# FlashMemory.net
KiCad netlist of a schematic drawn in Altium Designer
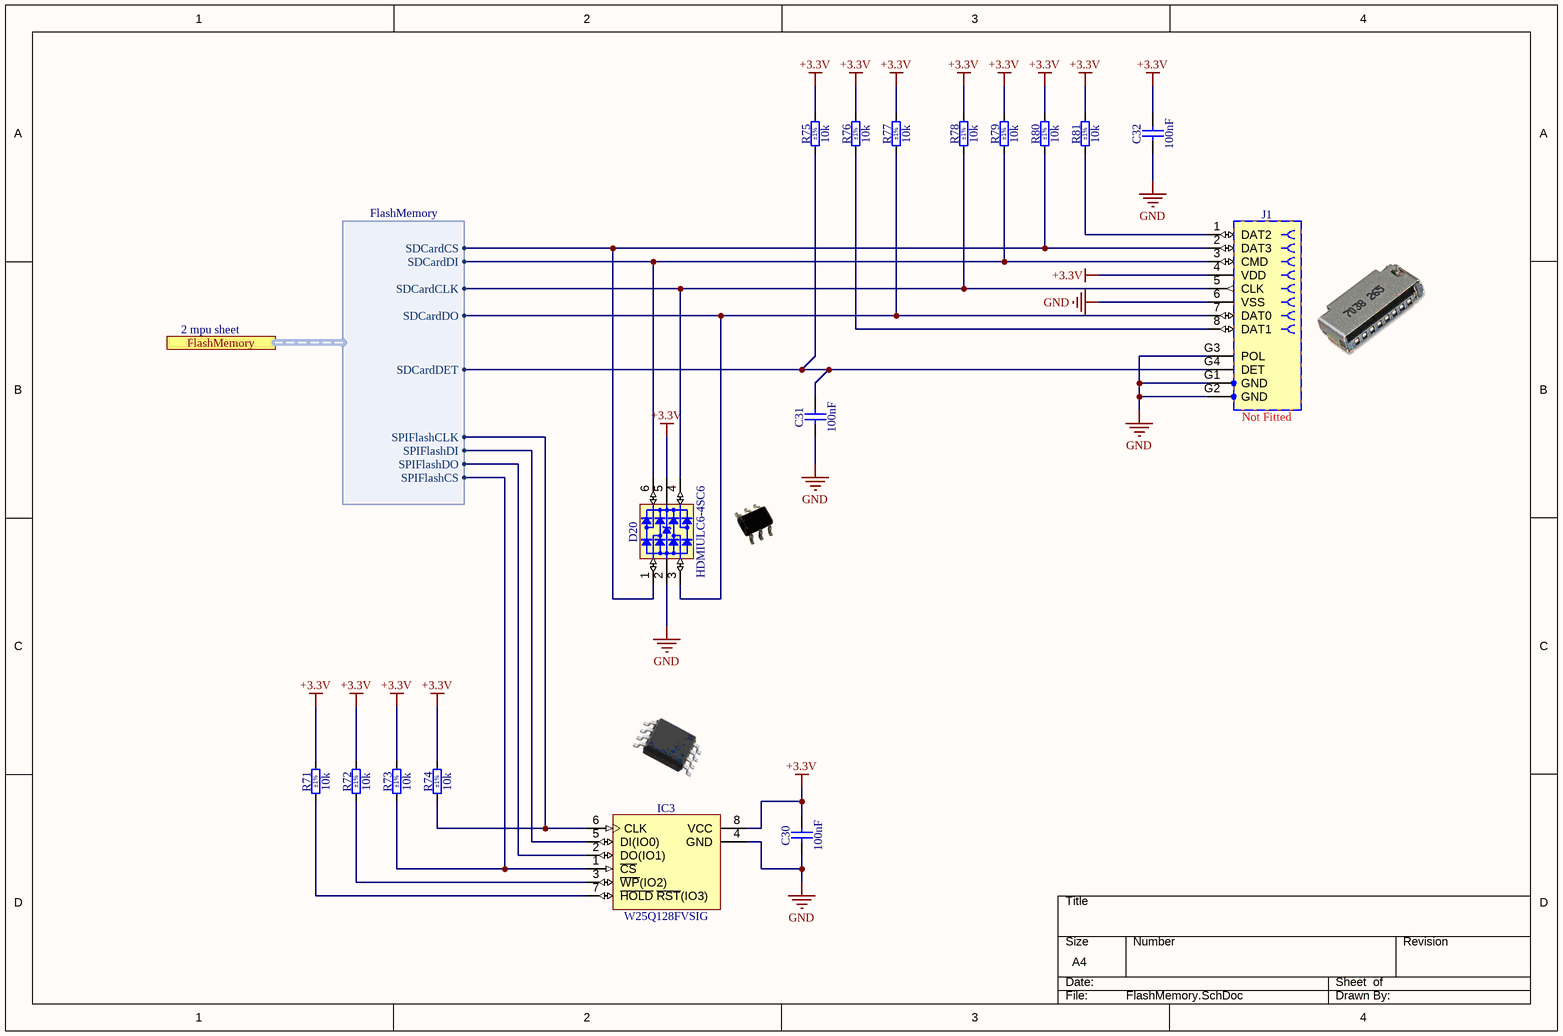
[diagram p0: FlashMemory.SchDoc]

(export (version "E")
  (design (tool "Eeschema 10.0.6"))
  (components
    (comp (ref "C30")
      (value "100nF")
      (footprint "CAPC1608X87N")
      (description "Non-polarised capacitor")
      (fields
        (field (name "PART NUMBER") "CC0603_100NF_50V_10%_X7R")
        (field (name "VOLTAGE") "50V")
        (field (name "AUTHOR") "CERN DEM JLC")
      )
      (libsource (lib "Capacitors") (part "Capacitor - non polarized"))
    )
    (comp (ref "C31")
      (value "100nF")
      (footprint "CAPC1608X87N")
      (description "Non-polarised capacitor")
      (fields
        (field (name "PART NUMBER") "CC0603_100NF_50V_10%_X7R")
        (field (name "VOLTAGE") "50V")
        (field (name "AUTHOR") "CERN DEM JLC")
      )
      (libsource (lib "Capacitors") (part "Capacitor - non polarized"))
    )
    (comp (ref "C32")
      (value "100nF")
      (footprint "CAPC1608X87N")
      (description "Non-polarised capacitor")
      (fields
        (field (name "PART NUMBER") "CC0603_100NF_50V_10%_X7R")
        (field (name "VOLTAGE") "50V")
        (field (name "AUTHOR") "CERN DEM JLC")
      )
      (libsource (lib "Capacitors") (part "Capacitor - non polarized"))
    )
    (comp (ref "D20")
      (value "HDMIULC6-4SC6")
      (footprint "SOT95P280X145-6N")
      (description "Ultra Large Bandwidth HDMI ESD Protection")
      (fields
        (field (name "VOLTAGE") "6V")
        (field (name "MANUFACTURER") "ST MICROELECTRONICS")
        (field (name "AUTHOR") "CERN DEM JLC")
      )
      (libsource (lib "ICs And Semiconductors") (part "HDMIULC6-4SC6"))
    )
    (comp (ref "IC3")
      (value "W25Q128FVSIG")
      (footprint "SOIC127P790X216-8N")
      (description "128M-bit Serial Flash Memory with uniform 4KB sectors and Dual/Quad SPI and QPI")
      (fields (field (name "MANUFACTURER") "WINBOND") (field (name "AUTHOR") "CERN DEM MR"))
      (libsource (lib "ICs And Semiconductors") (part "W25Q128FVSIG"))
    )
    (comp (ref "J1")
      (value "Not Fitted")
      (footprint "MOLEX_47309-2651")
      (description "MicroSD Card Header with Detect Switch")
      (fields
        (field (name "PART NUMBER") "MOLEX_47309-2651")
        (field (name "MANUFACTURER") "MOLEX")
        (field (name "AUTHOR") "CERN DEM JMW")
      )
      (libsource (lib "Connectors") (part "MOLEX_47309-2651"))
    )
    (comp (ref "R71")
      (value "10k")
      (footprint "RESC1608X55N")
      (description "Resistor - 1%")
      (fields
        (field (name "TOLERANCE") "±1%")
        (field (name "PART NUMBER") "R0603_10K_1%_0.1W_100PPM")
        (field (name "POWER") "0.1W")
        (field (name "AUTHOR") "CERN DEM JLC")
      )
      (libsource (lib "Resistors") (part "Resistor - 1%"))
    )
    (comp (ref "R72")
      (value "10k")
      (footprint "RESC1608X55N")
      (description "Resistor - 1%")
      (fields
        (field (name "TOLERANCE") "±1%")
        (field (name "PART NUMBER") "R0603_10K_1%_0.1W_100PPM")
        (field (name "POWER") "0.1W")
        (field (name "AUTHOR") "CERN DEM JLC")
      )
      (libsource (lib "Resistors") (part "Resistor - 1%"))
    )
    (comp (ref "R73")
      (value "10k")
      (footprint "RESC1608X55N")
      (description "Resistor - 1%")
      (fields
        (field (name "TOLERANCE") "±1%")
        (field (name "PART NUMBER") "R0603_10K_1%_0.1W_100PPM")
        (field (name "POWER") "0.1W")
        (field (name "AUTHOR") "CERN DEM JLC")
      )
      (libsource (lib "Resistors") (part "Resistor - 1%"))
    )
    (comp (ref "R74")
      (value "10k")
      (footprint "RESC1608X55N")
      (description "Resistor - 1%")
      (fields
        (field (name "TOLERANCE") "±1%")
        (field (name "PART NUMBER") "R0603_10K_1%_0.1W_100PPM")
        (field (name "POWER") "0.1W")
        (field (name "AUTHOR") "CERN DEM JLC")
      )
      (libsource (lib "Resistors") (part "Resistor - 1%"))
    )
    (comp (ref "R75")
      (value "10k")
      (footprint "RESC1608X55N")
      (description "Resistor - 1%")
      (fields
        (field (name "TOLERANCE") "±1%")
        (field (name "PART NUMBER") "R0603_10K_1%_0.1W_100PPM")
        (field (name "POWER") "0.1W")
        (field (name "AUTHOR") "CERN DEM JLC")
      )
      (libsource (lib "Resistors") (part "Resistor - 1%"))
    )
    (comp (ref "R76")
      (value "10k")
      (footprint "RESC1608X55N")
      (description "Resistor - 1%")
      (fields
        (field (name "TOLERANCE") "±1%")
        (field (name "PART NUMBER") "R0603_10K_1%_0.1W_100PPM")
        (field (name "POWER") "0.1W")
        (field (name "AUTHOR") "CERN DEM JLC")
      )
      (libsource (lib "Resistors") (part "Resistor - 1%"))
    )
    (comp (ref "R77")
      (value "10k")
      (footprint "RESC1608X55N")
      (description "Resistor - 1%")
      (fields
        (field (name "TOLERANCE") "±1%")
        (field (name "PART NUMBER") "R0603_10K_1%_0.1W_100PPM")
        (field (name "POWER") "0.1W")
        (field (name "AUTHOR") "CERN DEM JLC")
      )
      (libsource (lib "Resistors") (part "Resistor - 1%"))
    )
    (comp (ref "R78")
      (value "10k")
      (footprint "RESC1608X55N")
      (description "Resistor - 1%")
      (fields
        (field (name "TOLERANCE") "±1%")
        (field (name "PART NUMBER") "R0603_10K_1%_0.1W_100PPM")
        (field (name "POWER") "0.1W")
        (field (name "AUTHOR") "CERN DEM JLC")
      )
      (libsource (lib "Resistors") (part "Resistor - 1%"))
    )
    (comp (ref "R79")
      (value "10k")
      (footprint "RESC1608X55N")
      (description "Resistor - 1%")
      (fields
        (field (name "TOLERANCE") "±1%")
        (field (name "PART NUMBER") "R0603_10K_1%_0.1W_100PPM")
        (field (name "POWER") "0.1W")
        (field (name "AUTHOR") "CERN DEM JLC")
      )
      (libsource (lib "Resistors") (part "Resistor - 1%"))
    )
    (comp (ref "R80")
      (value "10k")
      (footprint "RESC1608X55N")
      (description "Resistor - 1%")
      (fields
        (field (name "TOLERANCE") "±1%")
        (field (name "PART NUMBER") "R0603_10K_1%_0.1W_100PPM")
        (field (name "POWER") "0.1W")
        (field (name "AUTHOR") "CERN DEM JLC")
      )
      (libsource (lib "Resistors") (part "Resistor - 1%"))
    )
    (comp (ref "R81")
      (value "10k")
      (footprint "RESC1608X55N")
      (description "Resistor - 1%")
      (fields
        (field (name "TOLERANCE") "±1%")
        (field (name "PART NUMBER") "R0603_10K_1%_0.1W_100PPM")
        (field (name "POWER") "0.1W")
        (field (name "AUTHOR") "CERN DEM JLC")
      )
      (libsource (lib "Resistors") (part "Resistor - 1%"))
    )
  )
  (nets
    (net (code "2") (name "+3.3V") (class "Default")
      (node (ref "C30") (pin "2") (pinfunction "2_2") (pintype "passive"))
      (node (ref "C32") (pin "2") (pinfunction "2_2") (pintype "passive"))
      (node (ref "D20") (pin "5") (pinfunction "VBUS_5") (pintype "power_in"))
      (node (ref "IC3") (pin "8") (pinfunction "VCC_8") (pintype "power_in"))
      (node (ref "J1") (pin "4") (pinfunction "VDD_4") (pintype "power_in"))
      (node (ref "R71") (pin "2") (pinfunction "2_2") (pintype "passive"))
      (node (ref "R72") (pin "2") (pinfunction "2_2") (pintype "passive"))
      (node (ref "R73") (pin "2") (pinfunction "2_2") (pintype "passive"))
      (node (ref "R74") (pin "2") (pinfunction "2_2") (pintype "passive"))
      (node (ref "R75") (pin "2") (pinfunction "2_2") (pintype "passive"))
      (node (ref "R76") (pin "2") (pinfunction "2_2") (pintype "passive"))
      (node (ref "R77") (pin "2") (pinfunction "2_2") (pintype "passive"))
      (node (ref "R78") (pin "2") (pinfunction "2_2") (pintype "passive"))
      (node (ref "R79") (pin "2") (pinfunction "2_2") (pintype "passive"))
      (node (ref "R80") (pin "2") (pinfunction "2_2") (pintype "passive"))
      (node (ref "R81") (pin "2") (pinfunction "2_2") (pintype "passive"))
    )
    (net (code "3") (name "/SDCardCLK") (class "Default")
      (node (ref "D20") (pin "4") (pinfunction "I/O3_4") (pintype "bidirectional"))
      (node (ref "J1") (pin "5") (pinfunction "CLK_5") (pintype "output"))
      (node (ref "R78") (pin "1") (pinfunction "1_1") (pintype "passive"))
    )
    (net (code "4") (name "/SDCardCS") (class "Default")
      (node (ref "D20") (pin "1") (pinfunction "I/O1_1") (pintype "bidirectional"))
      (node (ref "J1") (pin "2") (pinfunction "DAT3_2") (pintype "bidirectional"))
      (node (ref "R80") (pin "1") (pinfunction "1_1") (pintype "passive"))
    )
    (net (code "5") (name "/SDCardDET") (class "Default")
      (node (ref "C31") (pin "2") (pinfunction "2_2") (pintype "passive"))
      (node (ref "J1") (pin "G4") (pinfunction "DET_G4") (pintype "passive"))
      (node (ref "R75") (pin "1") (pinfunction "1_1") (pintype "passive"))
    )
    (net (code "6") (name "/SDCardDI") (class "Default")
      (node (ref "D20") (pin "6") (pinfunction "I/O4_6") (pintype "bidirectional"))
      (node (ref "J1") (pin "3") (pinfunction "CMD_3") (pintype "bidirectional"))
      (node (ref "R79") (pin "1") (pinfunction "1_1") (pintype "passive"))
    )
    (net (code "7") (name "/SDCardDO") (class "Default")
      (node (ref "D20") (pin "3") (pinfunction "I/O2_3") (pintype "bidirectional"))
      (node (ref "J1") (pin "7") (pinfunction "DAT0_7") (pintype "bidirectional"))
      (node (ref "R77") (pin "1") (pinfunction "1_1") (pintype "passive"))
    )
    (net (code "8") (name "/SPIFlashCLK") (class "Default")
      (node (ref "IC3") (pin "6") (pinfunction "CLK_6") (pintype "input"))
      (node (ref "R74") (pin "1") (pinfunction "1_1") (pintype "passive"))
    )
    (net (code "9") (name "/SPIFlashCS") (class "Default")
      (node (ref "IC3") (pin "1") (pinfunction "~{CS}_1") (pintype "input"))
      (node (ref "R73") (pin "1") (pinfunction "1_1") (pintype "passive"))
    )
    (net (code "10") (name "/SPIFlashDI") (class "Default")
      (node (ref "IC3") (pin "5") (pinfunction "DI(IO0)_5") (pintype "bidirectional"))
    )
    (net (code "11") (name "/SPIFlashDO") (class "Default")
      (node (ref "IC3") (pin "2") (pinfunction "DO(IO1)_2") (pintype "bidirectional"))
    )
    (net (code "13") (name "GND") (class "Default")
      (node (ref "C30") (pin "1") (pinfunction "1_1") (pintype "passive"))
      (node (ref "C31") (pin "1") (pinfunction "1_1") (pintype "passive"))
      (node (ref "C32") (pin "1") (pinfunction "1_1") (pintype "passive"))
      (node (ref "D20") (pin "2") (pinfunction "GND_2") (pintype "power_in"))
      (node (ref "IC3") (pin "4") (pinfunction "GND_4") (pintype "power_in"))
      (node (ref "J1") (pin "6") (pinfunction "VSS_6") (pintype "power_in"))
      (node (ref "J1") (pin "G1") (pinfunction "GND_G1") (pintype "passive"))
      (node (ref "J1") (pin "G2") (pinfunction "GND_G2") (pintype "passive"))
      (node (ref "J1") (pin "G3") (pinfunction "POL_G3") (pintype "passive"))
    )
    (net (code "14") (name "Net-(IC3-~{HOLD}_~{RST}(IO3))") (class "Default")
      (node (ref "IC3") (pin "7") (pinfunction "~{HOLD}_~{RST}(IO3)_7") (pintype "bidirectional"))
      (node (ref "R71") (pin "1") (pinfunction "1_1") (pintype "passive"))
    )
    (net (code "15") (name "Net-(IC3-~{WP}(IO2))") (class "Default")
      (node (ref "IC3") (pin "3") (pinfunction "~{WP}(IO2)_3") (pintype "bidirectional"))
      (node (ref "R72") (pin "1") (pinfunction "1_1") (pintype "passive"))
    )
    (net (code "16") (name "Net-(J1-DAT1)") (class "Default")
      (node (ref "J1") (pin "8") (pinfunction "DAT1_8") (pintype "bidirectional"))
      (node (ref "R76") (pin "1") (pinfunction "1_1") (pintype "passive"))
    )
    (net (code "17") (name "Net-(J1-DAT2)") (class "Default")
      (node (ref "J1") (pin "1") (pinfunction "DAT2_1") (pintype "bidirectional"))
      (node (ref "R81") (pin "1") (pinfunction "1_1") (pintype "passive"))
    )
  )
)
